# 24V_input.net
KiCad netlist of a schematic drawn in Altium Designer
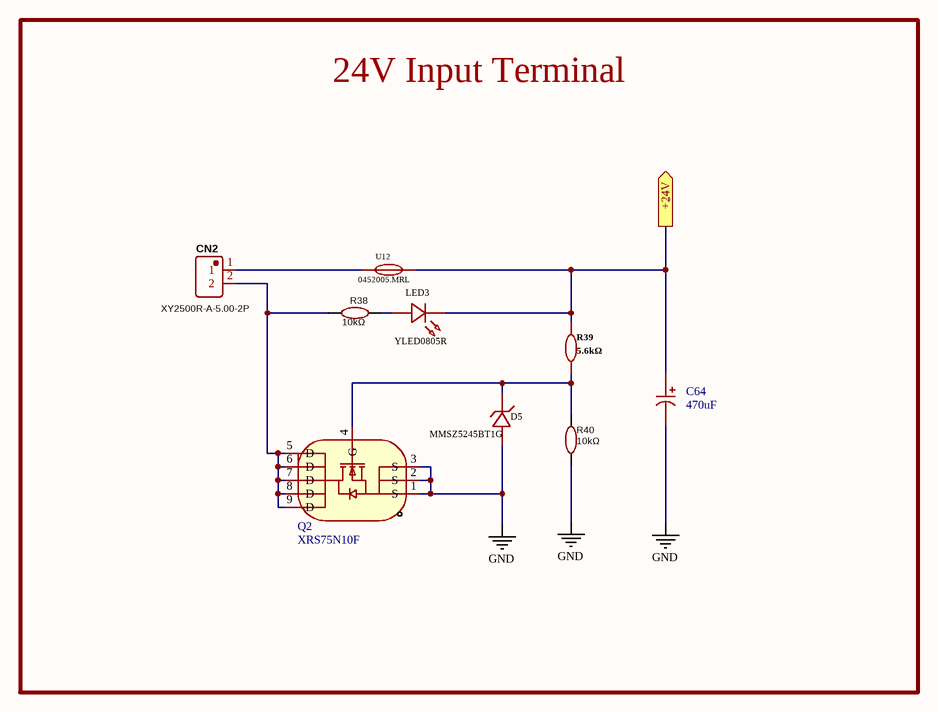
[diagram p0: 24V_input.SchDoc]

(export (version "E")
  (design (tool "Eeschema 10.0.6"))
  (components
    (comp (ref "C64")
      (value "470uF")
      (footprint "CAP-TH_BD10.0-P5.00-D0.6-FD_1")
      (fields
        (field (name "MANUFACTURER") "JIERR(捷而瑞)")
        (field (name "MANUFACTURER PART") "ERG35V470M10X16")
        (field (name "TOLERANCE") "±20%")
      )
      (libsource (lib "altium-import") (part "root_3_ERG35V470M10X16_"))
    )
    (comp (ref "CN2")
      (value "XY2500R-A-5.00-2P")
      (footprint "CONN-TH_XY2500R-A-5.00-2P")
      (fields (field (name "MANUFACTURER") "XINLAIYA(新莱亚)") (field (name "CONTRIBUTOR") "LCSC"))
      (libsource (lib "altium-import") (part "root_0_mirrored_XY2500R-A-5.00-2P_"))
    )
    (comp (ref "D5")
      (value "MMSZ5245BT1G")
      (footprint "SOD-123_L2.7-W1.6-LS3.7-RD")
      (fields (field (name "MANUFACTURER") "onsemi(安森美)"))
      (libsource (lib "altium-import") (part "root_3_MMSZ5245BT1G_"))
    )
    (comp (ref "LED3")
      (value "YLED0805R")
      (footprint "LED0805-RD_RED")
      (fields (field (name "MANUFACTURER") "YONGYUTAI(永裕泰)"))
      (libsource (lib "altium-import") (part "root_2_YLED0805R_"))
    )
    (comp (ref "Q2")
      (value "XRS75N10F")
      (footprint "PDFN-8_L5.8-W5.0-P1.27-LS6.1-BL")
      (fields (field (name "MANUFACTURER") "XNRUSEMI(新锐)"))
      (libsource (lib "altium-import") (part "root_2_XRS75N10F_"))
    )
    (comp (ref "R38")
      (value "10kΩ")
      (footprint "R_0603")
      (fields (field (name "MANUFACTURER") "YAGEO(国巨)") (field (name "MANUFACTURER PART") "RC0603FR-0710KL"))
      (libsource (lib "altium-import") (part "root_2_10kΩ_"))
    )
    (comp (ref "R39")
      (value "5.6kΩ")
      (footprint "R_0603")
      (fields
        (field (name "MANUFACTURER") "UNI-ROYAL(厚声)")
        (field (name "MANUFACTURER PART") "0603WAF5601T5E")
        (field (name "TOLERANCE") "±1%")
      )
      (libsource (lib "altium-import") (part "root_1_0603WAF5601T5E_"))
    )
    (comp (ref "R40")
      (value "10kΩ")
      (footprint "R_0603")
      (fields (field (name "MANUFACTURER") "YAGEO(国巨)") (field (name "MANUFACTURER PART") "RC0603FR-0710KL"))
      (libsource (lib "altium-import") (part "root_3_10kΩ_"))
    )
    (comp (ref "U12")
      (value "0452005.MRL")
      (footprint "FUSE-SMD_L6.1-W2.7")
      (fields (field (name "MANUFACTURER") "Littelfuse(美国力特)"))
      (libsource (lib "altium-import") (part "root_0_0452005.MRL_"))
    )
  )
  (nets
    (net (code "1") (name "/+24V") (class "Default")
      (node (ref "C64") (pin "1") (pinfunction "1_1") (pintype "passive"))
      (node (ref "LED3") (pin "1") (pinfunction "K_1") (pintype "passive"))
      (node (ref "R39") (pin "2") (pinfunction "2_2") (pintype "passive"))
      (node (ref "U12") (pin "2") (pinfunction "2_2") (pintype "passive"))
    )
    (net (code "2") (name "GND") (class "Default")
      (node (ref "C64") (pin "2") (pinfunction "2_2") (pintype "passive"))
      (node (ref "D5") (pin "2") (pinfunction "A_2") (pintype "passive"))
      (node (ref "Q2") (pin "1") (pinfunction "S_1") (pintype "passive"))
      (node (ref "Q2") (pin "2") (pinfunction "S_2") (pintype "passive"))
      (node (ref "Q2") (pin "3") (pinfunction "S_3") (pintype "passive"))
      (node (ref "R40") (pin "2") (pinfunction "2_2") (pintype "passive"))
    )
    (net (code "3") (name "Net-(CN2-Pad1)") (class "Default")
      (node (ref "CN2") (pin "1") (pinfunction "1_1") (pintype "passive"))
      (node (ref "U12") (pin "1") (pinfunction "1_1") (pintype "passive"))
    )
    (net (code "4") (name "Net-(CN2-Pad2)") (class "Default")
      (node (ref "CN2") (pin "2") (pinfunction "2_2") (pintype "passive"))
      (node (ref "Q2") (pin "5") (pinfunction "D_5") (pintype "passive"))
      (node (ref "Q2") (pin "6") (pinfunction "D_6") (pintype "passive"))
      (node (ref "Q2") (pin "7") (pinfunction "D_7") (pintype "passive"))
      (node (ref "Q2") (pin "8") (pinfunction "D_8") (pintype "passive"))
      (node (ref "Q2") (pin "9") (pinfunction "D_9") (pintype "passive"))
      (node (ref "R38") (pin "2") (pinfunction "2_2") (pintype "passive"))
    )
    (net (code "5") (name "Net-(D5-K)") (class "Default")
      (node (ref "D5") (pin "1") (pinfunction "K_1") (pintype "passive"))
      (node (ref "Q2") (pin "4") (pinfunction "G_4") (pintype "passive"))
      (node (ref "R39") (pin "1") (pinfunction "1_1") (pintype "passive"))
      (node (ref "R40") (pin "1") (pinfunction "1_1") (pintype "passive"))
    )
    (net (code "6") (name "Net-(LED3-A)") (class "Default")
      (node (ref "LED3") (pin "2") (pinfunction "A_2") (pintype "passive"))
      (node (ref "R38") (pin "1") (pinfunction "1_1") (pintype "passive"))
    )
  )
)
